# Activation_unfinished_easyeda.net
KiCad netlist of a schematic drawn in EasyEDA
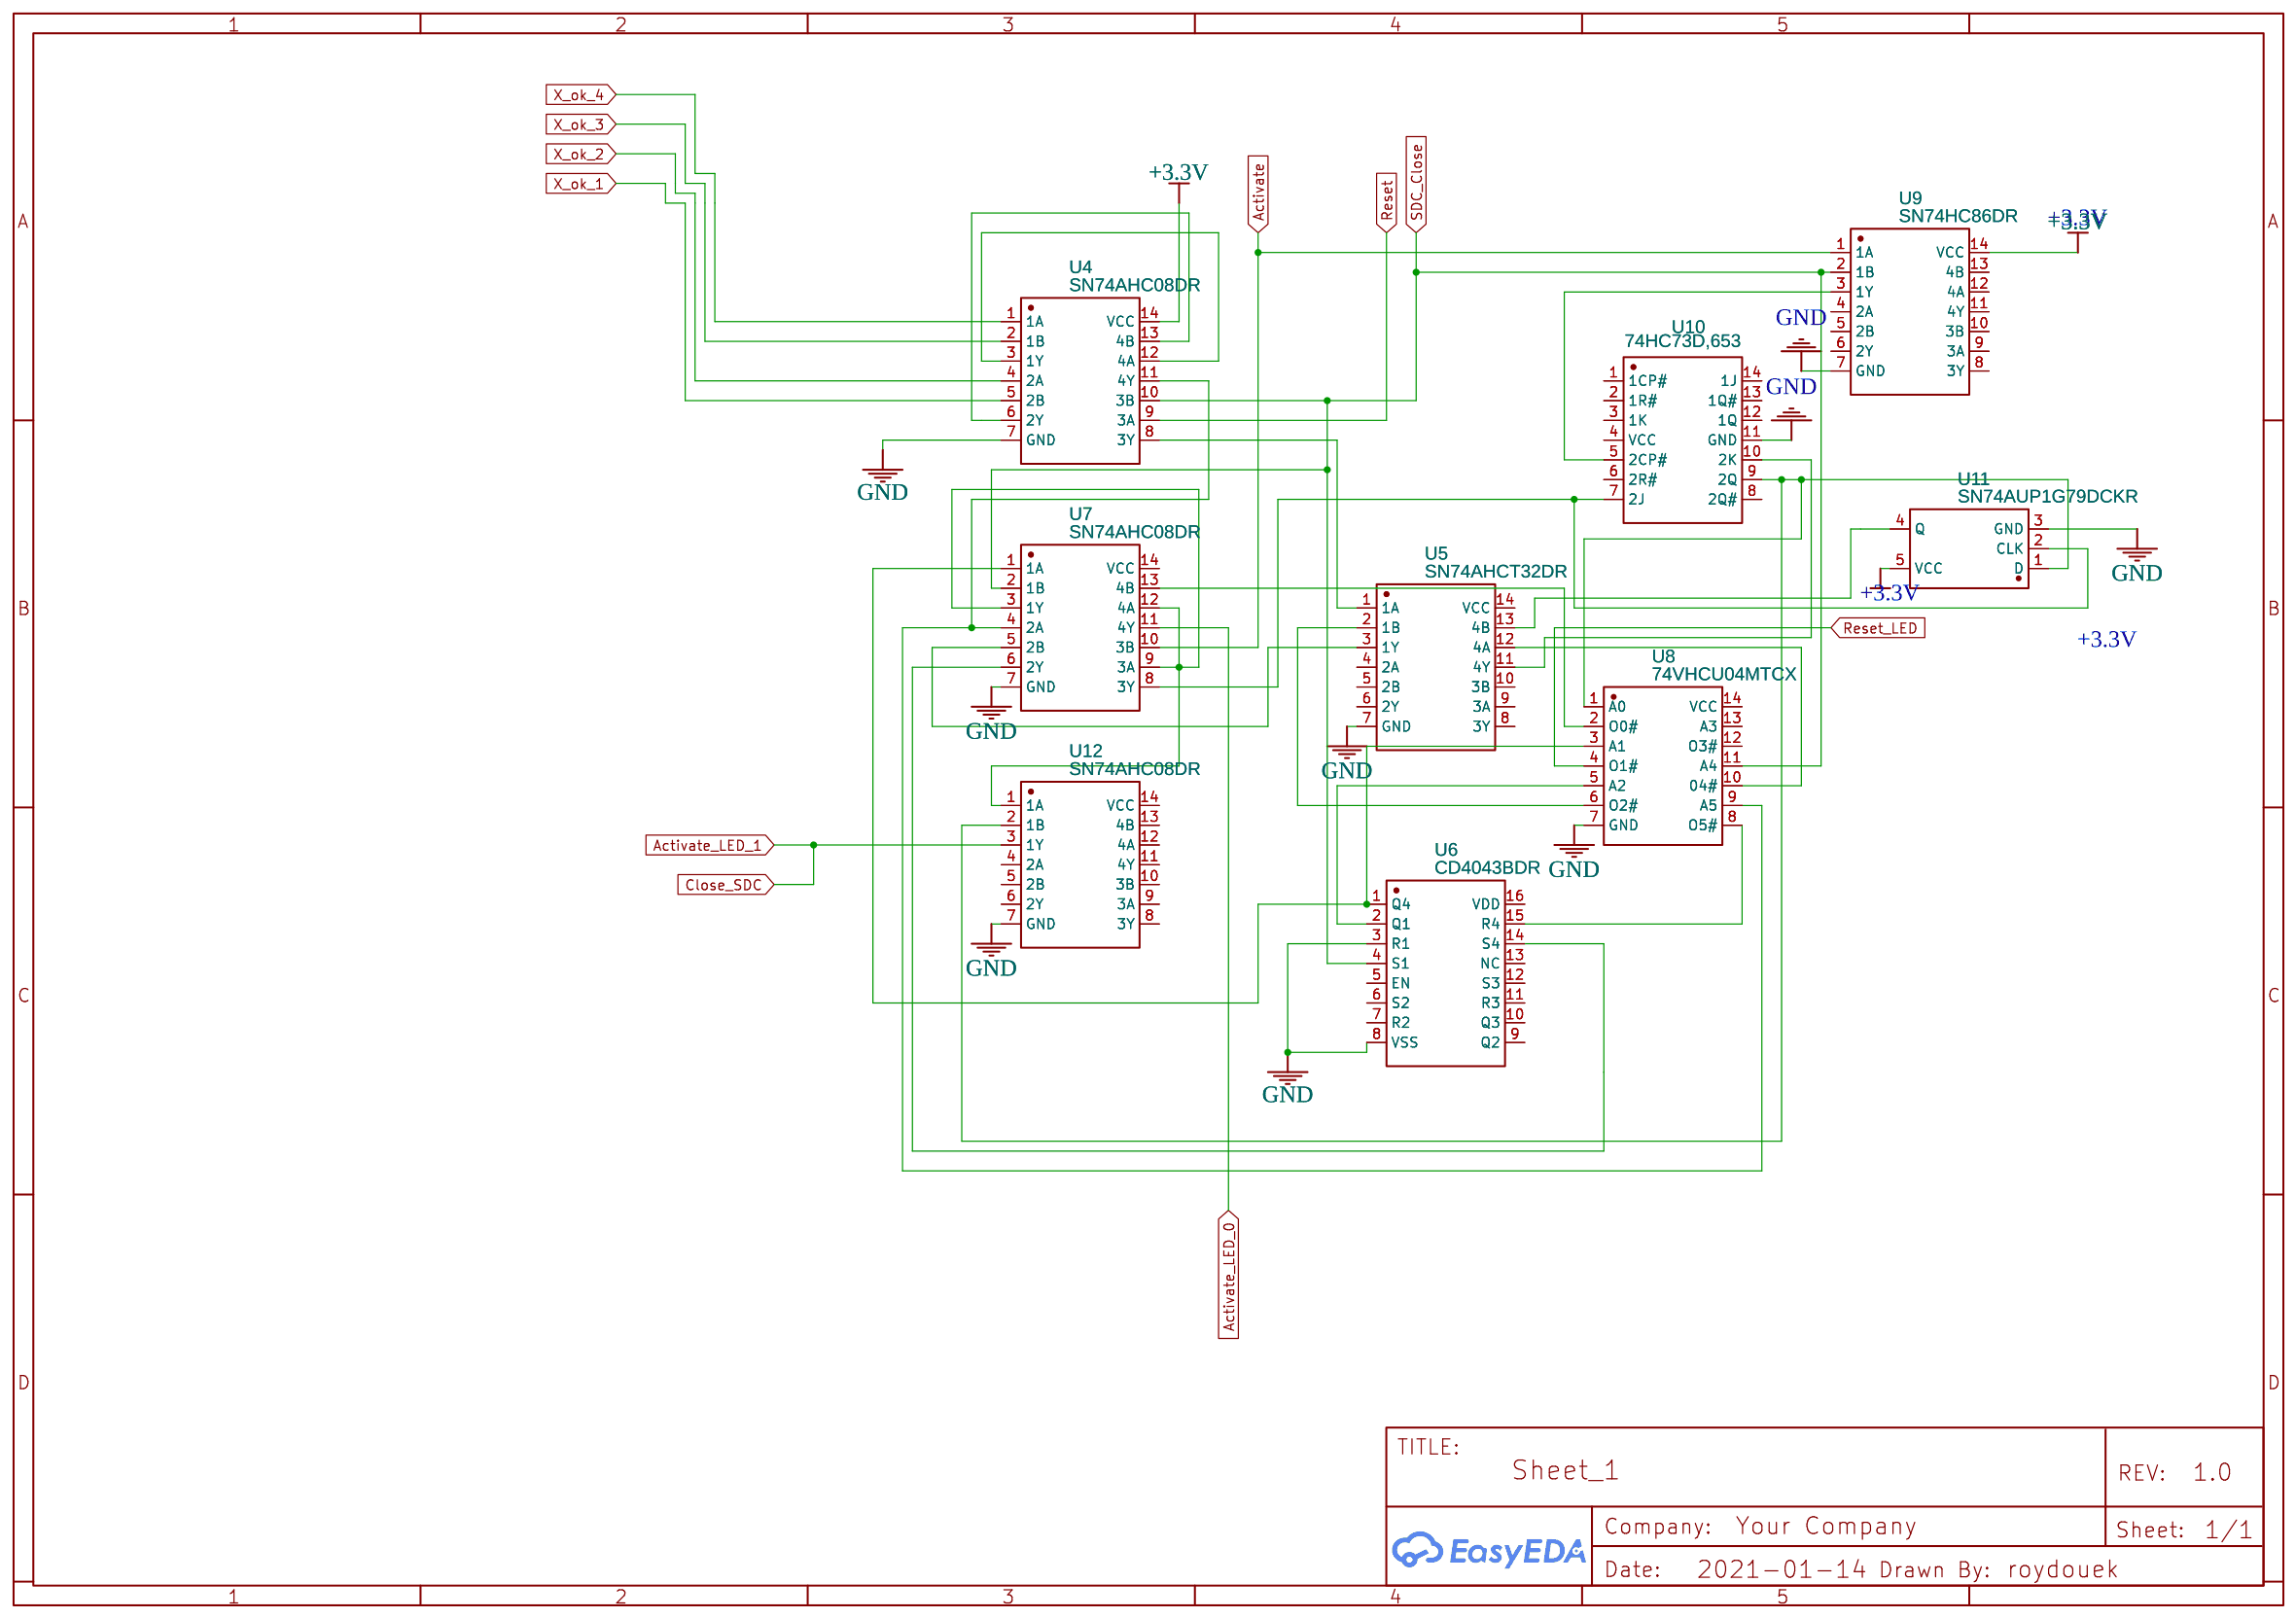
[diagram p0: schematic sheet]

(export (version "E")
  (design (tool "Eeschema 10.0.6"))
  (components
    (comp (ref "U4")
      (value "SN74AHC08DR")
      (fields (field (name "BOM_Supplier Part") "C6937"))
      (libsource (lib "") (part "SN74AHC08DR"))
    )
    (comp (ref "U5")
      (value "SN74AHCT32DR")
      (fields (field (name "BOM_Supplier Part") "C7490"))
      (libsource (lib "") (part "SN74AHCT32DR"))
    )
    (comp (ref "U6")
      (value "CD4043BDR")
      (fields (field (name "BOM_Supplier Part") "C40131"))
      (libsource (lib "") (part "CD4043BDR"))
    )
    (comp (ref "U7")
      (value "SN74AHC08DR")
      (fields (field (name "BOM_Supplier Part") "C6937"))
      (libsource (lib "") (part "SN74AHC08DR"))
    )
    (comp (ref "U8")
      (value "74VHCU04MTCX")
      (fields (field (name "BOM_Supplier Part") "C238971"))
      (libsource (lib "") (part "74VHCU04MTCX"))
    )
    (comp (ref "U9")
      (value "SN74HC86DR")
      (fields (field (name "BOM_Supplier Part") "C6763"))
      (libsource (lib "") (part "SN74HC86DR"))
    )
    (comp (ref "U10")
      (value "74HC73D,653")
      (fields (field (name "BOM_Supplier Part") "C148207"))
      (libsource (lib "") (part "74HC73D,653"))
    )
    (comp (ref "U11")
      (value "SN74AUP1G79DCKR")
      (fields (field (name "BOM_Supplier Part") "C206015"))
      (libsource (lib "") (part "SN74AUP1G79DCKR"))
    )
    (comp (ref "U12")
      (value "SN74AHC08DR")
      (fields (field (name "BOM_Supplier Part") "C6937"))
      (libsource (lib "") (part "SN74AHC08DR"))
    )
  )
  (nets
    (net (code "1") (name "+3.3V") (class "Default")
      (node (ref "U11") (pin "5") (pinfunction "VCC_5") (pintype "unspecified"))
      (node (ref "U4") (pin "14") (pinfunction "VCC_14") (pintype "unspecified"))
      (node (ref "U9") (pin "14") (pinfunction "VCC_14") (pintype "unspecified"))
    )
    (net (code "2") (name "Activate") (class "Default")
      (node (ref "U7") (pin "10") (pinfunction "3B_10") (pintype "unspecified"))
      (node (ref "U9") (pin "1") (pinfunction "1A_1") (pintype "unspecified"))
    )
    (net (code "3") (name "Activate_LED_0") (class "Default")
      (node (ref "U7") (pin "11") (pinfunction "4Y_11") (pintype "unspecified"))
    )
    (net (code "4") (name "Activate_LED_1") (class "Default")
      (node (ref "U12") (pin "3") (pinfunction "1Y_3") (pintype "unspecified"))
    )
    (net (code "5") (name "GND") (class "Default")
      (node (ref "U10") (pin "11") (pinfunction "GND_11") (pintype "unspecified"))
      (node (ref "U11") (pin "3") (pinfunction "GND_3") (pintype "unspecified"))
      (node (ref "U12") (pin "7") (pinfunction "GND_7") (pintype "unspecified"))
      (node (ref "U4") (pin "7") (pinfunction "GND_7") (pintype "unspecified"))
      (node (ref "U5") (pin "7") (pinfunction "GND_7") (pintype "unspecified"))
      (node (ref "U6") (pin "3") (pinfunction "R1_3") (pintype "unspecified"))
      (node (ref "U6") (pin "8") (pinfunction "VSS_8") (pintype "unspecified"))
      (node (ref "U7") (pin "7") (pinfunction "GND_7") (pintype "unspecified"))
      (node (ref "U8") (pin "7") (pinfunction "GND_7") (pintype "unspecified"))
      (node (ref "U9") (pin "7") (pinfunction "GND_7") (pintype "unspecified"))
    )
    (net (code "6") (name "Net-(U4-1Y)") (class "Default")
      (node (ref "U4") (pin "12") (pinfunction "4A_12") (pintype "unspecified"))
      (node (ref "U4") (pin "3") (pinfunction "1Y_3") (pintype "unspecified"))
    )
    (net (code "7") (name "Net-(U4-2Y)") (class "Default")
      (node (ref "U4") (pin "13") (pinfunction "4B_13") (pintype "unspecified"))
      (node (ref "U4") (pin "6") (pinfunction "2Y_6") (pintype "unspecified"))
    )
    (net (code "8") (name "Net-(U4-3Y)") (class "Default")
      (node (ref "U4") (pin "8") (pinfunction "3Y_8") (pintype "unspecified"))
      (node (ref "U5") (pin "1") (pinfunction "1A_1") (pintype "unspecified"))
    )
    (net (code "9") (name "Net-(U4-4Y)") (class "Default")
      (node (ref "U4") (pin "11") (pinfunction "4Y_11") (pintype "unspecified"))
      (node (ref "U7") (pin "4") (pinfunction "2A_4") (pintype "unspecified"))
      (node (ref "U8") (pin "9") (pinfunction "A5_9") (pintype "unspecified"))
    )
    (net (code "10") (name "Net-(U5-1B)") (class "Default")
      (node (ref "U5") (pin "2") (pinfunction "1B_2") (pintype "unspecified"))
      (node (ref "U8") (pin "6") (pinfunction "O2#_6") (pintype "unspecified"))
    )
    (net (code "11") (name "Net-(U5-1Y)") (class "Default")
      (node (ref "U5") (pin "3") (pinfunction "1Y_3") (pintype "unspecified"))
      (node (ref "U7") (pin "5") (pinfunction "2B_5") (pintype "unspecified"))
    )
    (net (code "12") (name "Net-(U5-4A)") (class "Default")
      (node (ref "U5") (pin "12") (pinfunction "4A_12") (pintype "unspecified"))
      (node (ref "U8") (pin "10") (pinfunction "04#_10") (pintype "unspecified"))
    )
    (net (code "13") (name "Net-(U6-Q1)") (class "Default")
      (node (ref "U6") (pin "2") (pinfunction "Q1_2") (pintype "unspecified"))
      (node (ref "U8") (pin "5") (pinfunction "A2_5") (pintype "unspecified"))
    )
    (net (code "14") (name "Net-(U6-Q4)") (class "Default")
      (node (ref "U6") (pin "1") (pinfunction "Q4_1") (pintype "unspecified"))
      (node (ref "U7") (pin "1") (pinfunction "1A_1") (pintype "unspecified"))
      (node (ref "U8") (pin "3") (pinfunction "A1_3") (pintype "unspecified"))
    )
    (net (code "15") (name "Net-(U6-R4)") (class "Default")
      (node (ref "U6") (pin "15") (pinfunction "R4_15") (pintype "unspecified"))
      (node (ref "U8") (pin "8") (pinfunction "O5#_8") (pintype "unspecified"))
    )
    (net (code "16") (name "Net-(U6-S4)") (class "Default")
      (node (ref "U6") (pin "14") (pinfunction "S4_14") (pintype "unspecified"))
      (node (ref "U7") (pin "6") (pinfunction "2Y_6") (pintype "unspecified"))
    )
    (net (code "17") (name "Net-(U7-4B)") (class "Default")
      (node (ref "U7") (pin "13") (pinfunction "4B_13") (pintype "unspecified"))
      (node (ref "U8") (pin "2") (pinfunction "O0#_2") (pintype "unspecified"))
    )
    (net (code "18") (name "Net-(U10-2CP#)") (class "Default")
      (node (ref "U10") (pin "5") (pinfunction "2CP#_5") (pintype "unspecified"))
      (node (ref "U9") (pin "3") (pinfunction "1Y_3") (pintype "unspecified"))
    )
    (net (code "19") (name "Net-(U10-2J)") (class "Default")
      (node (ref "U10") (pin "7") (pinfunction "2J_7") (pintype "unspecified"))
      (node (ref "U11") (pin "2") (pinfunction "CLK_2") (pintype "unspecified"))
      (node (ref "U7") (pin "8") (pinfunction "3Y_8") (pintype "unspecified"))
    )
    (net (code "20") (name "Net-(U10-2K)") (class "Default")
      (node (ref "U10") (pin "10") (pinfunction "2K_10") (pintype "unspecified"))
      (node (ref "U5") (pin "11") (pinfunction "4Y_11") (pintype "unspecified"))
    )
    (net (code "21") (name "Net-(U10-2Q)") (class "Default")
      (node (ref "U10") (pin "9") (pinfunction "2Q_9") (pintype "unspecified"))
      (node (ref "U11") (pin "1") (pinfunction "D_1") (pintype "unspecified"))
      (node (ref "U12") (pin "2") (pinfunction "1B_2") (pintype "unspecified"))
      (node (ref "U8") (pin "1") (pinfunction "A0_1") (pintype "unspecified"))
    )
    (net (code "22") (name "Net-(U11-Q)") (class "Default")
      (node (ref "U11") (pin "4") (pinfunction "Q_4") (pintype "unspecified"))
      (node (ref "U5") (pin "13") (pinfunction "4B_13") (pintype "unspecified"))
    )
    (net (code "23") (name "Net-(U12-1A)") (class "Default")
      (node (ref "U12") (pin "1") (pinfunction "1A_1") (pintype "unspecified"))
      (node (ref "U7") (pin "12") (pinfunction "4A_12") (pintype "unspecified"))
      (node (ref "U7") (pin "3") (pinfunction "1Y_3") (pintype "unspecified"))
      (node (ref "U7") (pin "9") (pinfunction "3A_9") (pintype "unspecified"))
    )
    (net (code "24") (name "Reset") (class "Default")
      (node (ref "U4") (pin "9") (pinfunction "3A_9") (pintype "unspecified"))
    )
    (net (code "25") (name "Reset_LED") (class "Default")
      (node (ref "U8") (pin "4") (pinfunction "O1#_4") (pintype "unspecified"))
    )
    (net (code "26") (name "SDC_Close") (class "Default")
      (node (ref "U4") (pin "10") (pinfunction "3B_10") (pintype "unspecified"))
      (node (ref "U6") (pin "4") (pinfunction "S1_4") (pintype "unspecified"))
      (node (ref "U7") (pin "2") (pinfunction "1B_2") (pintype "unspecified"))
      (node (ref "U8") (pin "11") (pinfunction "A4_11") (pintype "unspecified"))
      (node (ref "U9") (pin "2") (pinfunction "1B_2") (pintype "unspecified"))
    )
    (net (code "27") (name "X_ok_1") (class "Default")
      (node (ref "U4") (pin "5") (pinfunction "2B_5") (pintype "unspecified"))
    )
    (net (code "28") (name "X_ok_2") (class "Default")
      (node (ref "U4") (pin "4") (pinfunction "2A_4") (pintype "unspecified"))
    )
    (net (code "29") (name "X_ok_3") (class "Default")
      (node (ref "U4") (pin "2") (pinfunction "1B_2") (pintype "unspecified"))
    )
    (net (code "30") (name "X_ok_4") (class "Default")
      (node (ref "U4") (pin "1") (pinfunction "1A_1") (pintype "unspecified"))
    )
    (net (code "31") (name "unconnected-(U5-2A-Pad4)") (class "Default")
      (node (ref "U5") (pin "4") (pinfunction "2A_4") (pintype "unspecified"))
    )
    (net (code "32") (name "unconnected-(U5-2B-Pad5)") (class "Default")
      (node (ref "U5") (pin "5") (pinfunction "2B_5") (pintype "unspecified"))
    )
    (net (code "33") (name "unconnected-(U5-2Y-Pad6)") (class "Default")
      (node (ref "U5") (pin "6") (pinfunction "2Y_6") (pintype "unspecified"))
    )
    (net (code "34") (name "unconnected-(U5-3A-Pad9)") (class "Default")
      (node (ref "U5") (pin "9") (pinfunction "3A_9") (pintype "unspecified"))
    )
    (net (code "35") (name "unconnected-(U5-3B-Pad10)") (class "Default")
      (node (ref "U5") (pin "10") (pinfunction "3B_10") (pintype "unspecified"))
    )
    (net (code "36") (name "unconnected-(U5-3Y-Pad8)") (class "Default")
      (node (ref "U5") (pin "8") (pinfunction "3Y_8") (pintype "unspecified"))
    )
    (net (code "37") (name "unconnected-(U5-VCC-Pad14)") (class "Default")
      (node (ref "U5") (pin "14") (pinfunction "VCC_14") (pintype "unspecified"))
    )
    (net (code "38") (name "unconnected-(U6-EN-Pad5)") (class "Default")
      (node (ref "U6") (pin "5") (pinfunction "EN_5") (pintype "unspecified"))
    )
    (net (code "39") (name "unconnected-(U6-NC-Pad13)") (class "Default")
      (node (ref "U6") (pin "13") (pinfunction "NC_13") (pintype "unspecified"))
    )
    (net (code "40") (name "unconnected-(U6-Q2-Pad9)") (class "Default")
      (node (ref "U6") (pin "9") (pinfunction "Q2_9") (pintype "unspecified"))
    )
    (net (code "41") (name "unconnected-(U6-Q3-Pad10)") (class "Default")
      (node (ref "U6") (pin "10") (pinfunction "Q3_10") (pintype "unspecified"))
    )
    (net (code "42") (name "unconnected-(U6-R2-Pad7)") (class "Default")
      (node (ref "U6") (pin "7") (pinfunction "R2_7") (pintype "unspecified"))
    )
    (net (code "43") (name "unconnected-(U6-R3-Pad11)") (class "Default")
      (node (ref "U6") (pin "11") (pinfunction "R3_11") (pintype "unspecified"))
    )
    (net (code "44") (name "unconnected-(U6-S2-Pad6)") (class "Default")
      (node (ref "U6") (pin "6") (pinfunction "S2_6") (pintype "unspecified"))
    )
    (net (code "45") (name "unconnected-(U6-S3-Pad12)") (class "Default")
      (node (ref "U6") (pin "12") (pinfunction "S3_12") (pintype "unspecified"))
    )
    (net (code "46") (name "unconnected-(U6-VDD-Pad16)") (class "Default")
      (node (ref "U6") (pin "16") (pinfunction "VDD_16") (pintype "unspecified"))
    )
    (net (code "47") (name "unconnected-(U7-VCC-Pad14)") (class "Default")
      (node (ref "U7") (pin "14") (pinfunction "VCC_14") (pintype "unspecified"))
    )
    (net (code "48") (name "unconnected-(U8-A3-Pad13)") (class "Default")
      (node (ref "U8") (pin "13") (pinfunction "A3_13") (pintype "unspecified"))
    )
    (net (code "49") (name "unconnected-(U8-O3#-Pad12)") (class "Default")
      (node (ref "U8") (pin "12") (pinfunction "O3#_12") (pintype "unspecified"))
    )
    (net (code "50") (name "unconnected-(U8-VCC-Pad14)") (class "Default")
      (node (ref "U8") (pin "14") (pinfunction "VCC_14") (pintype "unspecified"))
    )
    (net (code "51") (name "unconnected-(U9-2A-Pad4)") (class "Default")
      (node (ref "U9") (pin "4") (pinfunction "2A_4") (pintype "unspecified"))
    )
    (net (code "52") (name "unconnected-(U9-2B-Pad5)") (class "Default")
      (node (ref "U9") (pin "5") (pinfunction "2B_5") (pintype "unspecified"))
    )
    (net (code "53") (name "unconnected-(U9-2Y-Pad6)") (class "Default")
      (node (ref "U9") (pin "6") (pinfunction "2Y_6") (pintype "unspecified"))
    )
    (net (code "54") (name "unconnected-(U9-3A-Pad9)") (class "Default")
      (node (ref "U9") (pin "9") (pinfunction "3A_9") (pintype "unspecified"))
    )
    (net (code "55") (name "unconnected-(U9-3B-Pad10)") (class "Default")
      (node (ref "U9") (pin "10") (pinfunction "3B_10") (pintype "unspecified"))
    )
    (net (code "56") (name "unconnected-(U9-3Y-Pad8)") (class "Default")
      (node (ref "U9") (pin "8") (pinfunction "3Y_8") (pintype "unspecified"))
    )
    (net (code "57") (name "unconnected-(U9-4A-Pad12)") (class "Default")
      (node (ref "U9") (pin "12") (pinfunction "4A_12") (pintype "unspecified"))
    )
    (net (code "58") (name "unconnected-(U9-4B-Pad13)") (class "Default")
      (node (ref "U9") (pin "13") (pinfunction "4B_13") (pintype "unspecified"))
    )
    (net (code "59") (name "unconnected-(U9-4Y-Pad11)") (class "Default")
      (node (ref "U9") (pin "11") (pinfunction "4Y_11") (pintype "unspecified"))
    )
    (net (code "60") (name "unconnected-(U10-1CP#-Pad1)") (class "Default")
      (node (ref "U10") (pin "1") (pinfunction "1CP#_1") (pintype "unspecified"))
    )
    (net (code "61") (name "unconnected-(U10-1J-Pad14)") (class "Default")
      (node (ref "U10") (pin "14") (pinfunction "1J_14") (pintype "unspecified"))
    )
    (net (code "62") (name "unconnected-(U10-1K-Pad3)") (class "Default")
      (node (ref "U10") (pin "3") (pinfunction "1K_3") (pintype "unspecified"))
    )
    (net (code "63") (name "unconnected-(U10-1Q#-Pad13)") (class "Default")
      (node (ref "U10") (pin "13") (pinfunction "1Q#_13") (pintype "unspecified"))
    )
    (net (code "64") (name "unconnected-(U10-1Q-Pad12)") (class "Default")
      (node (ref "U10") (pin "12") (pinfunction "1Q_12") (pintype "unspecified"))
    )
    (net (code "65") (name "unconnected-(U10-1R#-Pad2)") (class "Default")
      (node (ref "U10") (pin "2") (pinfunction "1R#_2") (pintype "unspecified"))
    )
    (net (code "66") (name "unconnected-(U10-2Q#-Pad8)") (class "Default")
      (node (ref "U10") (pin "8") (pinfunction "2Q#_8") (pintype "unspecified"))
    )
    (net (code "67") (name "unconnected-(U10-2R#-Pad6)") (class "Default")
      (node (ref "U10") (pin "6") (pinfunction "2R#_6") (pintype "unspecified"))
    )
    (net (code "68") (name "unconnected-(U10-VCC-Pad4)") (class "Default")
      (node (ref "U10") (pin "4") (pinfunction "VCC_4") (pintype "unspecified"))
    )
    (net (code "69") (name "unconnected-(U12-2A-Pad4)") (class "Default")
      (node (ref "U12") (pin "4") (pinfunction "2A_4") (pintype "unspecified"))
    )
    (net (code "70") (name "unconnected-(U12-2B-Pad5)") (class "Default")
      (node (ref "U12") (pin "5") (pinfunction "2B_5") (pintype "unspecified"))
    )
    (net (code "71") (name "unconnected-(U12-2Y-Pad6)") (class "Default")
      (node (ref "U12") (pin "6") (pinfunction "2Y_6") (pintype "unspecified"))
    )
    (net (code "72") (name "unconnected-(U12-3A-Pad9)") (class "Default")
      (node (ref "U12") (pin "9") (pinfunction "3A_9") (pintype "unspecified"))
    )
    (net (code "73") (name "unconnected-(U12-3B-Pad10)") (class "Default")
      (node (ref "U12") (pin "10") (pinfunction "3B_10") (pintype "unspecified"))
    )
    (net (code "74") (name "unconnected-(U12-3Y-Pad8)") (class "Default")
      (node (ref "U12") (pin "8") (pinfunction "3Y_8") (pintype "unspecified"))
    )
    (net (code "75") (name "unconnected-(U12-4A-Pad12)") (class "Default")
      (node (ref "U12") (pin "12") (pinfunction "4A_12") (pintype "unspecified"))
    )
    (net (code "76") (name "unconnected-(U12-4B-Pad13)") (class "Default")
      (node (ref "U12") (pin "13") (pinfunction "4B_13") (pintype "unspecified"))
    )
    (net (code "77") (name "unconnected-(U12-4Y-Pad11)") (class "Default")
      (node (ref "U12") (pin "11") (pinfunction "4Y_11") (pintype "unspecified"))
    )
    (net (code "78") (name "unconnected-(U12-VCC-Pad14)") (class "Default")
      (node (ref "U12") (pin "14") (pinfunction "VCC_14") (pintype "unspecified"))
    )
  )
)
